# OGX360I-2CH_-_USB_PCB.net
KiCad netlist of a schematic drawn in EAGLE
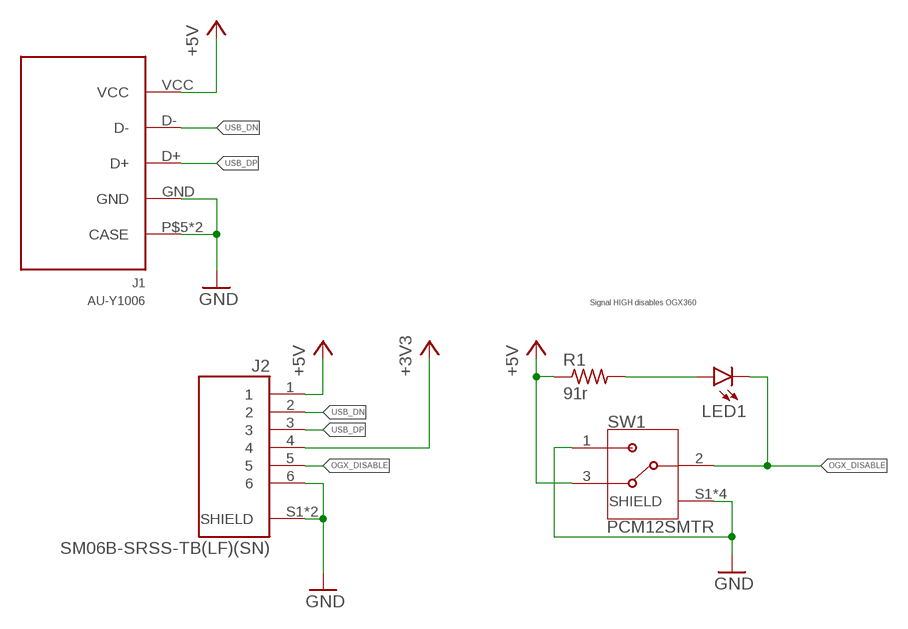
[diagram p0: schematic, sheet 1]

(export (version "E")
  (design (tool "Eeschema 10.0.6"))
  (components
    (comp (ref "J1")
      (value "AU-Y1006")
      (footprint "eagle-import:USBA_SMD")
      (fields (field (name "MF") "Assmann WSW"))
      (libsource (lib "eagle-import") (part "AU-Y1006"))
    )
    (comp (ref "J2")
      (value "SM06B-SRSS-TB(LF)(SN)")
      (footprint "eagle-import:JST_SM06B-SRSS-TB(LF)(SN)")
      (fields
        (field (name "DIGI-KEY_PART_NUMBER") "455-1806-1-ND")
        (field (name "MF") "JST Sales")
        (field (name "MP") "SM06B-SRSS-TB_LF__SN_")
      )
      (libsource (lib "eagle-import") (part "SM06B-SRSS-TB(LF)(SN)"))
    )
    (comp (ref "LED1")
      (value "LEDCHIP-LED0805")
      (footprint "eagle-import:CHIP-LED0805")
      (libsource (lib "eagle-import") (part "LEDCHIP-LED0805"))
    )
    (comp (ref "R1")
      (value "91r")
      (footprint "eagle-import:R0805")
      (libsource (lib "eagle-import") (part "R-US_R0805"))
    )
    (comp (ref "SW1")
      (value "PCM12SMTR")
      (footprint "eagle-import:SW_PCM12SMTR")
      (fields (field (name "DIGI-KEY_PART_NUMBER") "401-2016-1-ND") (field (name "MF") "C&K"))
      (libsource (lib "eagle-import") (part "PCM12SMTR"))
    )
  )
  (nets
    (net (code "1") (name "+3V3") (class "Default")
      (node (ref "J2") (pin "4") (pinfunction "4_4") (pintype "passive"))
    )
    (net (code "2") (name "+5V") (class "Default")
      (node (ref "J1") (pin "VCC") (pinfunction "VCC_VCC") (pintype "bidirectional"))
      (node (ref "J2") (pin "1") (pinfunction "1_1") (pintype "passive"))
      (node (ref "R1") (pin "1") (pinfunction "1_1") (pintype "passive"))
      (node (ref "SW1") (pin "3") (pinfunction "3_3") (pintype "passive"))
    )
    (net (code "3") (name "GND") (class "Default")
      (node (ref "J1") (pin "GND") (pinfunction "GND_GND") (pintype "bidirectional"))
      (node (ref "J1") (pin "P$5") (pinfunction "CASE_P$5") (pintype "bidirectional"))
      (node (ref "J1") (pin "P$6") (pinfunction "CASE_P$6") (pintype "bidirectional"))
      (node (ref "J2") (pin "6") (pinfunction "6_6") (pintype "passive"))
      (node (ref "J2") (pin "S1") (pinfunction "SHIELD_S1") (pintype "passive"))
      (node (ref "J2") (pin "S2") (pinfunction "SHIELD_S2") (pintype "passive"))
      (node (ref "SW1") (pin "1") (pinfunction "1_1") (pintype "passive"))
      (node (ref "SW1") (pin "S1") (pinfunction "SHIELD_S1") (pintype "passive"))
      (node (ref "SW1") (pin "S2") (pinfunction "SHIELD_S2") (pintype "passive"))
      (node (ref "SW1") (pin "S3") (pinfunction "SHIELD_S3") (pintype "passive"))
      (node (ref "SW1") (pin "S4") (pinfunction "SHIELD_S4") (pintype "passive"))
    )
    (net (code "4") (name "Net-(LED1-PadA)") (class "Default")
      (node (ref "LED1") (pin "A") (pinfunction "A_A") (pintype "passive"))
      (node (ref "R1") (pin "2") (pinfunction "2_2") (pintype "passive"))
    )
    (net (code "5") (name "OGX_DISABLE") (class "Default")
      (node (ref "J2") (pin "5") (pinfunction "5_5") (pintype "passive"))
      (node (ref "LED1") (pin "C") (pinfunction "C_C") (pintype "passive"))
      (node (ref "SW1") (pin "2") (pinfunction "2_2") (pintype "passive"))
    )
    (net (code "6") (name "USB_DN") (class "Default")
      (node (ref "J1") (pin "D-") (pinfunction "D-_D-") (pintype "bidirectional"))
      (node (ref "J2") (pin "2") (pinfunction "2_2") (pintype "passive"))
    )
    (net (code "7") (name "USB_DP") (class "Default")
      (node (ref "J1") (pin "D+") (pinfunction "D+_D+") (pintype "bidirectional"))
      (node (ref "J2") (pin "3") (pinfunction "3_3") (pintype "passive"))
    )
  )
)
